# Enconder_Part1.net
KiCad netlist of a schematic drawn in Altium Designer
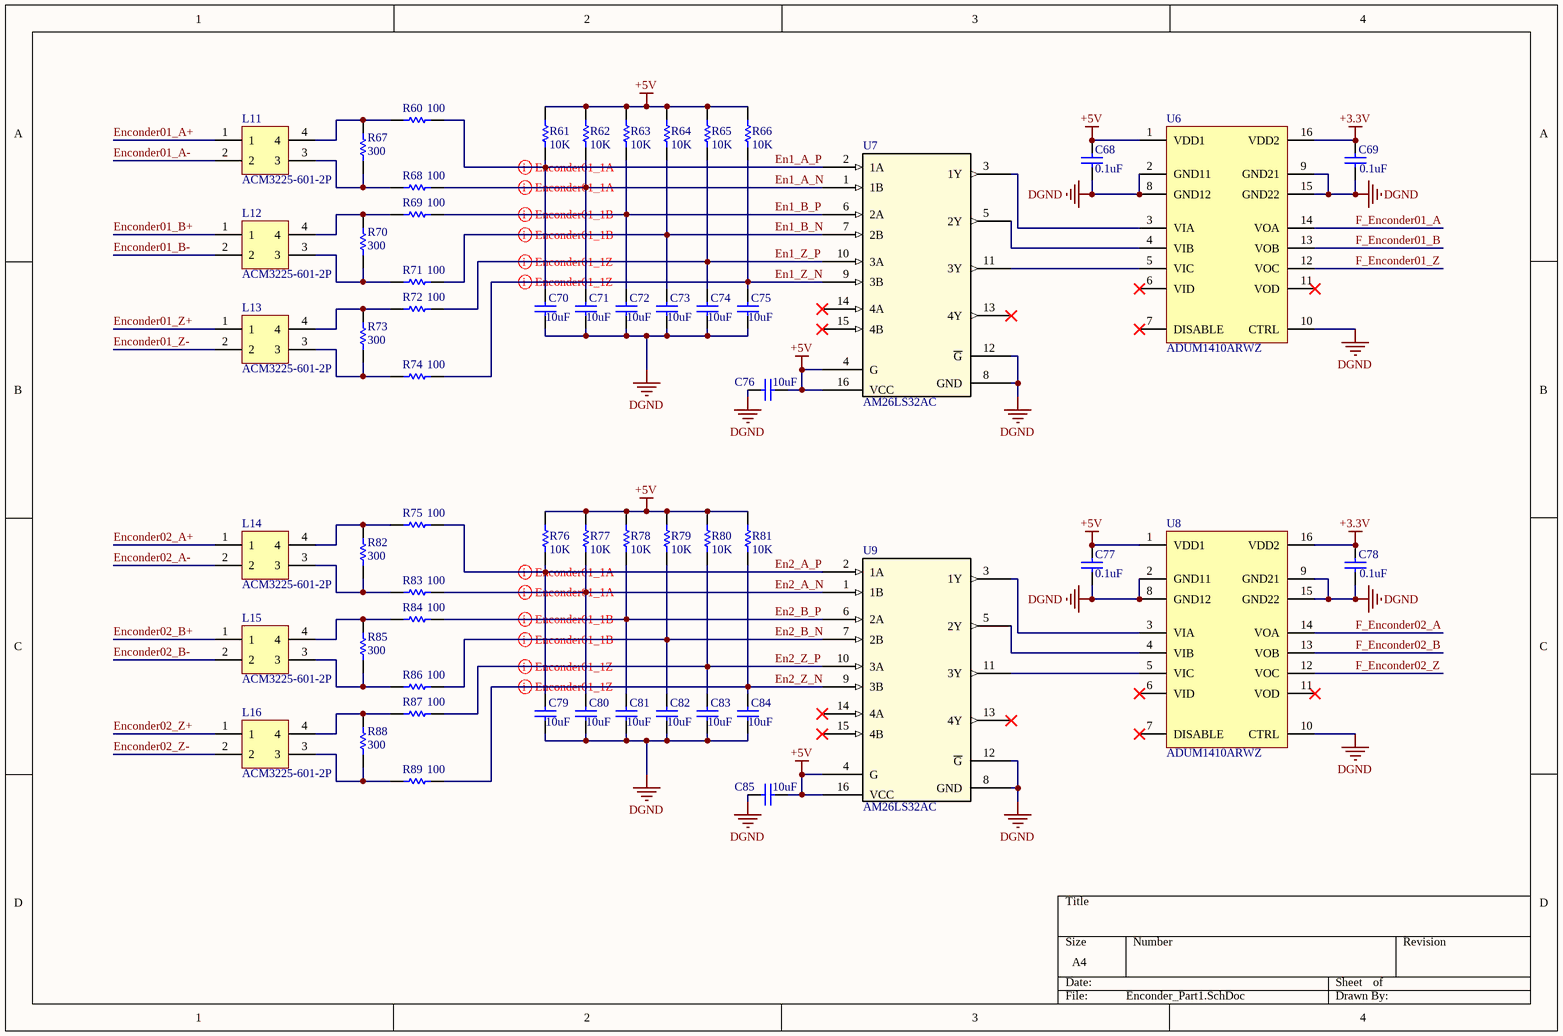
[diagram p0: Enconder_Part1.SchDoc]

(export (version "E")
  (design (tool "Eeschema 10.0.6"))
  (components
    (comp (ref "C68")
      (value "0.1uF")
      (footprint "1608[0603]")
      (description "Capacitor")
      (fields (field (name "Comment") "Cap") (field (name "PUBLISHER") "Altium Limited"))
      (libsource (lib "Miscellaneous Devices") (part "Cap"))
    )
    (comp (ref "C69")
      (value "0.1uF")
      (footprint "1608[0603]")
      (description "Capacitor")
      (fields (field (name "Comment") "Cap") (field (name "PUBLISHER") "Altium Limited"))
      (libsource (lib "Miscellaneous Devices") (part "Cap"))
    )
    (comp (ref "C70")
      (value "10uF")
      (footprint "1608[0603]")
      (description "Capacitor")
      (fields (field (name "Comment") "Cap") (field (name "PUBLISHER") "Altium Limited"))
      (libsource (lib "Miscellaneous Devices") (part "Cap"))
    )
    (comp (ref "C71")
      (value "10uF")
      (footprint "1608[0603]")
      (description "Capacitor")
      (fields (field (name "Comment") "Cap") (field (name "PUBLISHER") "Altium Limited"))
      (libsource (lib "Miscellaneous Devices") (part "Cap"))
    )
    (comp (ref "C72")
      (value "10uF")
      (footprint "1608[0603]")
      (description "Capacitor")
      (fields (field (name "Comment") "Cap") (field (name "PUBLISHER") "Altium Limited"))
      (libsource (lib "Miscellaneous Devices") (part "Cap"))
    )
    (comp (ref "C73")
      (value "10uF")
      (footprint "1608[0603]")
      (description "Capacitor")
      (fields (field (name "Comment") "Cap") (field (name "PUBLISHER") "Altium Limited"))
      (libsource (lib "Miscellaneous Devices") (part "Cap"))
    )
    (comp (ref "C74")
      (value "10uF")
      (footprint "1608[0603]")
      (description "Capacitor")
      (fields (field (name "Comment") "Cap") (field (name "PUBLISHER") "Altium Limited"))
      (libsource (lib "Miscellaneous Devices") (part "Cap"))
    )
    (comp (ref "C75")
      (value "10uF")
      (footprint "1608[0603]")
      (description "Capacitor")
      (fields (field (name "Comment") "Cap") (field (name "PUBLISHER") "Altium Limited"))
      (libsource (lib "Miscellaneous Devices") (part "Cap"))
    )
    (comp (ref "C76")
      (value "10uF")
      (footprint "1608[0603]")
      (description "Capacitor")
      (fields (field (name "Comment") "Cap") (field (name "PUBLISHER") "Altium Limited"))
      (libsource (lib "Miscellaneous Devices") (part "Cap"))
    )
    (comp (ref "C77")
      (value "0.1uF")
      (footprint "1608[0603]")
      (description "Capacitor")
      (fields (field (name "Comment") "Cap") (field (name "PUBLISHER") "Altium Limited"))
      (libsource (lib "Miscellaneous Devices") (part "Cap"))
    )
    (comp (ref "C78")
      (value "0.1uF")
      (footprint "1608[0603]")
      (description "Capacitor")
      (fields (field (name "Comment") "Cap") (field (name "PUBLISHER") "Altium Limited"))
      (libsource (lib "Miscellaneous Devices") (part "Cap"))
    )
    (comp (ref "C79")
      (value "10uF")
      (footprint "1608[0603]")
      (description "Capacitor")
      (fields (field (name "Comment") "Cap") (field (name "PUBLISHER") "Altium Limited"))
      (libsource (lib "Miscellaneous Devices") (part "Cap"))
    )
    (comp (ref "C80")
      (value "10uF")
      (footprint "1608[0603]")
      (description "Capacitor")
      (fields (field (name "Comment") "Cap") (field (name "PUBLISHER") "Altium Limited"))
      (libsource (lib "Miscellaneous Devices") (part "Cap"))
    )
    (comp (ref "C81")
      (value "10uF")
      (footprint "1608[0603]")
      (description "Capacitor")
      (fields (field (name "Comment") "Cap") (field (name "PUBLISHER") "Altium Limited"))
      (libsource (lib "Miscellaneous Devices") (part "Cap"))
    )
    (comp (ref "C82")
      (value "10uF")
      (footprint "1608[0603]")
      (description "Capacitor")
      (fields (field (name "Comment") "Cap") (field (name "PUBLISHER") "Altium Limited"))
      (libsource (lib "Miscellaneous Devices") (part "Cap"))
    )
    (comp (ref "C83")
      (value "10uF")
      (footprint "1608[0603]")
      (description "Capacitor")
      (fields (field (name "Comment") "Cap") (field (name "PUBLISHER") "Altium Limited"))
      (libsource (lib "Miscellaneous Devices") (part "Cap"))
    )
    (comp (ref "C84")
      (value "10uF")
      (footprint "1608[0603]")
      (description "Capacitor")
      (fields (field (name "Comment") "Cap") (field (name "PUBLISHER") "Altium Limited"))
      (libsource (lib "Miscellaneous Devices") (part "Cap"))
    )
    (comp (ref "C85")
      (value "10uF")
      (footprint "1608[0603]")
      (description "Capacitor")
      (fields (field (name "Comment") "Cap") (field (name "PUBLISHER") "Altium Limited"))
      (libsource (lib "Miscellaneous Devices") (part "Cap"))
    )
    (comp (ref "L11")
      (value "ACM3225-601-2P")
      (footprint "ACM3225-601-2P")
      (libsource (lib "DSP_FPGA_Lib") (part "ACM3225-601-2P"))
    )
    (comp (ref "L12")
      (value "ACM3225-601-2P")
      (footprint "ACM3225-601-2P")
      (libsource (lib "DSP_FPGA_Lib") (part "ACM3225-601-2P"))
    )
    (comp (ref "L13")
      (value "ACM3225-601-2P")
      (footprint "ACM3225-601-2P")
      (libsource (lib "DSP_FPGA_Lib") (part "ACM3225-601-2P"))
    )
    (comp (ref "L14")
      (value "ACM3225-601-2P")
      (footprint "ACM3225-601-2P")
      (libsource (lib "DSP_FPGA_Lib") (part "ACM3225-601-2P"))
    )
    (comp (ref "L15")
      (value "ACM3225-601-2P")
      (footprint "ACM3225-601-2P")
      (libsource (lib "DSP_FPGA_Lib") (part "ACM3225-601-2P"))
    )
    (comp (ref "L16")
      (value "ACM3225-601-2P")
      (footprint "ACM3225-601-2P")
      (libsource (lib "DSP_FPGA_Lib") (part "ACM3225-601-2P"))
    )
    (comp (ref "R60")
      (value "100")
      (footprint "1608[0603]")
      (description "Resistor")
      (fields (field (name "Comment") "Res1") (field (name "PUBLISHER") "Altium Limited"))
      (libsource (lib "Miscellaneous Devices") (part "Res1"))
    )
    (comp (ref "R61")
      (value "10K")
      (footprint "1608[0603]")
      (description "Resistor")
      (fields (field (name "Comment") "Res1") (field (name "PUBLISHER") "Altium Limited"))
      (libsource (lib "Miscellaneous Devices") (part "Res1"))
    )
    (comp (ref "R62")
      (value "10K")
      (footprint "1608[0603]")
      (description "Resistor")
      (fields (field (name "Comment") "Res1") (field (name "PUBLISHER") "Altium Limited"))
      (libsource (lib "Miscellaneous Devices") (part "Res1"))
    )
    (comp (ref "R63")
      (value "10K")
      (footprint "1608[0603]")
      (description "Resistor")
      (fields (field (name "Comment") "Res1") (field (name "PUBLISHER") "Altium Limited"))
      (libsource (lib "Miscellaneous Devices") (part "Res1"))
    )
    (comp (ref "R64")
      (value "10K")
      (footprint "1608[0603]")
      (description "Resistor")
      (fields (field (name "Comment") "Res1") (field (name "PUBLISHER") "Altium Limited"))
      (libsource (lib "Miscellaneous Devices") (part "Res1"))
    )
    (comp (ref "R65")
      (value "10K")
      (footprint "1608[0603]")
      (description "Resistor")
      (fields (field (name "Comment") "Res1") (field (name "PUBLISHER") "Altium Limited"))
      (libsource (lib "Miscellaneous Devices") (part "Res1"))
    )
    (comp (ref "R66")
      (value "10K")
      (footprint "1608[0603]")
      (description "Resistor")
      (fields (field (name "Comment") "Res1") (field (name "PUBLISHER") "Altium Limited"))
      (libsource (lib "Miscellaneous Devices") (part "Res1"))
    )
    (comp (ref "R67")
      (value "300")
      (footprint "1608[0603]")
      (description "Resistor")
      (fields (field (name "Comment") "Res1") (field (name "PUBLISHER") "Altium Limited"))
      (libsource (lib "Miscellaneous Devices") (part "Res1"))
    )
    (comp (ref "R68")
      (value "100")
      (footprint "1608[0603]")
      (description "Resistor")
      (fields (field (name "Comment") "Res1") (field (name "PUBLISHER") "Altium Limited"))
      (libsource (lib "Miscellaneous Devices") (part "Res1"))
    )
    (comp (ref "R69")
      (value "100")
      (footprint "1608[0603]")
      (description "Resistor")
      (fields (field (name "Comment") "Res1") (field (name "PUBLISHER") "Altium Limited"))
      (libsource (lib "Miscellaneous Devices") (part "Res1"))
    )
    (comp (ref "R70")
      (value "300")
      (footprint "1608[0603]")
      (description "Resistor")
      (fields (field (name "Comment") "Res1") (field (name "PUBLISHER") "Altium Limited"))
      (libsource (lib "Miscellaneous Devices") (part "Res1"))
    )
    (comp (ref "R71")
      (value "100")
      (footprint "1608[0603]")
      (description "Resistor")
      (fields (field (name "Comment") "Res1") (field (name "PUBLISHER") "Altium Limited"))
      (libsource (lib "Miscellaneous Devices") (part "Res1"))
    )
    (comp (ref "R72")
      (value "100")
      (footprint "1608[0603]")
      (description "Resistor")
      (fields (field (name "Comment") "Res1") (field (name "PUBLISHER") "Altium Limited"))
      (libsource (lib "Miscellaneous Devices") (part "Res1"))
    )
    (comp (ref "R73")
      (value "300")
      (footprint "1608[0603]")
      (description "Resistor")
      (fields (field (name "Comment") "Res1") (field (name "PUBLISHER") "Altium Limited"))
      (libsource (lib "Miscellaneous Devices") (part "Res1"))
    )
    (comp (ref "R74")
      (value "100")
      (footprint "1608[0603]")
      (description "Resistor")
      (fields (field (name "Comment") "Res1") (field (name "PUBLISHER") "Altium Limited"))
      (libsource (lib "Miscellaneous Devices") (part "Res1"))
    )
    (comp (ref "R75")
      (value "100")
      (footprint "1608[0603]")
      (description "Resistor")
      (fields (field (name "Comment") "Res1") (field (name "PUBLISHER") "Altium Limited"))
      (libsource (lib "Miscellaneous Devices") (part "Res1"))
    )
    (comp (ref "R76")
      (value "10K")
      (footprint "1608[0603]")
      (description "Resistor")
      (fields (field (name "Comment") "Res1") (field (name "PUBLISHER") "Altium Limited"))
      (libsource (lib "Miscellaneous Devices") (part "Res1"))
    )
    (comp (ref "R77")
      (value "10K")
      (footprint "1608[0603]")
      (description "Resistor")
      (fields (field (name "Comment") "Res1") (field (name "PUBLISHER") "Altium Limited"))
      (libsource (lib "Miscellaneous Devices") (part "Res1"))
    )
    (comp (ref "R78")
      (value "10K")
      (footprint "1608[0603]")
      (description "Resistor")
      (fields (field (name "Comment") "Res1") (field (name "PUBLISHER") "Altium Limited"))
      (libsource (lib "Miscellaneous Devices") (part "Res1"))
    )
    (comp (ref "R79")
      (value "10K")
      (footprint "1608[0603]")
      (description "Resistor")
      (fields (field (name "Comment") "Res1") (field (name "PUBLISHER") "Altium Limited"))
      (libsource (lib "Miscellaneous Devices") (part "Res1"))
    )
    (comp (ref "R80")
      (value "10K")
      (footprint "1608[0603]")
      (description "Resistor")
      (fields (field (name "Comment") "Res1") (field (name "PUBLISHER") "Altium Limited"))
      (libsource (lib "Miscellaneous Devices") (part "Res1"))
    )
    (comp (ref "R81")
      (value "10K")
      (footprint "1608[0603]")
      (description "Resistor")
      (fields (field (name "Comment") "Res1") (field (name "PUBLISHER") "Altium Limited"))
      (libsource (lib "Miscellaneous Devices") (part "Res1"))
    )
    (comp (ref "R82")
      (value "300")
      (footprint "1608[0603]")
      (description "Resistor")
      (fields (field (name "Comment") "Res1") (field (name "PUBLISHER") "Altium Limited"))
      (libsource (lib "Miscellaneous Devices") (part "Res1"))
    )
    (comp (ref "R83")
      (value "100")
      (footprint "1608[0603]")
      (description "Resistor")
      (fields (field (name "Comment") "Res1") (field (name "PUBLISHER") "Altium Limited"))
      (libsource (lib "Miscellaneous Devices") (part "Res1"))
    )
    (comp (ref "R84")
      (value "100")
      (footprint "1608[0603]")
      (description "Resistor")
      (fields (field (name "Comment") "Res1") (field (name "PUBLISHER") "Altium Limited"))
      (libsource (lib "Miscellaneous Devices") (part "Res1"))
    )
    (comp (ref "R85")
      (value "300")
      (footprint "1608[0603]")
      (description "Resistor")
      (fields (field (name "Comment") "Res1") (field (name "PUBLISHER") "Altium Limited"))
      (libsource (lib "Miscellaneous Devices") (part "Res1"))
    )
    (comp (ref "R86")
      (value "100")
      (footprint "1608[0603]")
      (description "Resistor")
      (fields (field (name "Comment") "Res1") (field (name "PUBLISHER") "Altium Limited"))
      (libsource (lib "Miscellaneous Devices") (part "Res1"))
    )
    (comp (ref "R87")
      (value "100")
      (footprint "1608[0603]")
      (description "Resistor")
      (fields (field (name "Comment") "Res1") (field (name "PUBLISHER") "Altium Limited"))
      (libsource (lib "Miscellaneous Devices") (part "Res1"))
    )
    (comp (ref "R88")
      (value "300")
      (footprint "1608[0603]")
      (description "Resistor")
      (fields (field (name "Comment") "Res1") (field (name "PUBLISHER") "Altium Limited"))
      (libsource (lib "Miscellaneous Devices") (part "Res1"))
    )
    (comp (ref "R89")
      (value "100")
      (footprint "1608[0603]")
      (description "Resistor")
      (fields (field (name "Comment") "Res1") (field (name "PUBLISHER") "Altium Limited"))
      (libsource (lib "Miscellaneous Devices") (part "Res1"))
    )
    (comp (ref "U6")
      (value "ADUM1410ARWZ")
      (footprint "ADUM1410ARWZ_SOIC")
      (libsource (lib "DSP_FPGA_Lib") (part "ADUM1410ARWZ"))
    )
    (comp (ref "U7")
      (value "AM26LS32AC")
      (footprint "AM26LS32AC_SOP")
      (libsource (lib "DSP_FPGA_Lib") (part "AM26LS32AC"))
    )
    (comp (ref "U8")
      (value "ADUM1410ARWZ")
      (footprint "ADUM1410ARWZ_SOIC")
      (libsource (lib "DSP_FPGA_Lib") (part "ADUM1410ARWZ"))
    )
    (comp (ref "U9")
      (value "AM26LS32AC")
      (footprint "AM26LS32AC_SOP")
      (libsource (lib "DSP_FPGA_Lib") (part "AM26LS32AC"))
    )
  )
  (nets
    (net (code "1") (name "+3.3V") (class "Default")
      (node (ref "C69") (pin "2") (pinfunction "2_2") (pintype "passive"))
      (node (ref "C78") (pin "2") (pinfunction "2_2") (pintype "passive"))
      (node (ref "U6") (pin "16") (pinfunction "VDD2_16") (pintype "passive"))
      (node (ref "U8") (pin "16") (pinfunction "VDD2_16") (pintype "passive"))
    )
    (net (code "2") (name "+5V") (class "Default")
      (node (ref "C68") (pin "2") (pinfunction "2_2") (pintype "passive"))
      (node (ref "C76") (pin "1") (pinfunction "1_1") (pintype "passive"))
      (node (ref "C77") (pin "2") (pinfunction "2_2") (pintype "passive"))
      (node (ref "C85") (pin "1") (pinfunction "1_1") (pintype "passive"))
      (node (ref "R61") (pin "2") (pinfunction "2_2") (pintype "passive"))
      (node (ref "R62") (pin "2") (pinfunction "2_2") (pintype "passive"))
      (node (ref "R63") (pin "2") (pinfunction "2_2") (pintype "passive"))
      (node (ref "R64") (pin "2") (pinfunction "2_2") (pintype "passive"))
      (node (ref "R65") (pin "2") (pinfunction "2_2") (pintype "passive"))
      (node (ref "R66") (pin "2") (pinfunction "2_2") (pintype "passive"))
      (node (ref "R76") (pin "2") (pinfunction "2_2") (pintype "passive"))
      (node (ref "R77") (pin "2") (pinfunction "2_2") (pintype "passive"))
      (node (ref "R78") (pin "2") (pinfunction "2_2") (pintype "passive"))
      (node (ref "R79") (pin "2") (pinfunction "2_2") (pintype "passive"))
      (node (ref "R80") (pin "2") (pinfunction "2_2") (pintype "passive"))
      (node (ref "R81") (pin "2") (pinfunction "2_2") (pintype "passive"))
      (node (ref "U6") (pin "1") (pinfunction "VDD1_1") (pintype "passive"))
      (node (ref "U7") (pin "16") (pinfunction "VCC_16") (pintype "power_in"))
      (node (ref "U7") (pin "4") (pinfunction "G_4") (pintype "passive"))
      (node (ref "U8") (pin "1") (pinfunction "VDD1_1") (pintype "passive"))
      (node (ref "U9") (pin "16") (pinfunction "VCC_16") (pintype "power_in"))
      (node (ref "U9") (pin "4") (pinfunction "G_4") (pintype "passive"))
    )
    (net (code "3") (name "/En1_A_N") (class "Default")
      (node (ref "C71") (pin "2") (pinfunction "2_2") (pintype "passive"))
      (node (ref "R62") (pin "1") (pinfunction "1_1") (pintype "passive"))
      (node (ref "R68") (pin "2") (pinfunction "2_2") (pintype "passive"))
      (node (ref "U7") (pin "1") (pinfunction "1B_1") (pintype "input"))
    )
    (net (code "4") (name "/En1_A_P") (class "Default")
      (node (ref "C70") (pin "2") (pinfunction "2_2") (pintype "passive"))
      (node (ref "R60") (pin "2") (pinfunction "2_2") (pintype "passive"))
      (node (ref "R61") (pin "1") (pinfunction "1_1") (pintype "passive"))
      (node (ref "U7") (pin "2") (pinfunction "1A_2") (pintype "input"))
    )
    (net (code "5") (name "/En1_B_N") (class "Default")
      (node (ref "C73") (pin "2") (pinfunction "2_2") (pintype "passive"))
      (node (ref "R64") (pin "1") (pinfunction "1_1") (pintype "passive"))
      (node (ref "R71") (pin "2") (pinfunction "2_2") (pintype "passive"))
      (node (ref "U7") (pin "7") (pinfunction "2B_7") (pintype "input"))
    )
    (net (code "6") (name "/En1_B_P") (class "Default")
      (node (ref "C72") (pin "2") (pinfunction "2_2") (pintype "passive"))
      (node (ref "R63") (pin "1") (pinfunction "1_1") (pintype "passive"))
      (node (ref "R69") (pin "2") (pinfunction "2_2") (pintype "passive"))
      (node (ref "U7") (pin "6") (pinfunction "2A_6") (pintype "input"))
    )
    (net (code "7") (name "/En1_Z_N") (class "Default")
      (node (ref "C75") (pin "2") (pinfunction "2_2") (pintype "passive"))
      (node (ref "R66") (pin "1") (pinfunction "1_1") (pintype "passive"))
      (node (ref "R74") (pin "2") (pinfunction "2_2") (pintype "passive"))
      (node (ref "U7") (pin "9") (pinfunction "3B_9") (pintype "input"))
    )
    (net (code "8") (name "/En1_Z_P") (class "Default")
      (node (ref "C74") (pin "2") (pinfunction "2_2") (pintype "passive"))
      (node (ref "R65") (pin "1") (pinfunction "1_1") (pintype "passive"))
      (node (ref "R72") (pin "2") (pinfunction "2_2") (pintype "passive"))
      (node (ref "U7") (pin "10") (pinfunction "3A_10") (pintype "input"))
    )
    (net (code "9") (name "/En2_A_N") (class "Default")
      (node (ref "C80") (pin "2") (pinfunction "2_2") (pintype "passive"))
      (node (ref "R77") (pin "1") (pinfunction "1_1") (pintype "passive"))
      (node (ref "R83") (pin "2") (pinfunction "2_2") (pintype "passive"))
      (node (ref "U9") (pin "1") (pinfunction "1B_1") (pintype "input"))
    )
    (net (code "10") (name "/En2_A_P") (class "Default")
      (node (ref "C79") (pin "2") (pinfunction "2_2") (pintype "passive"))
      (node (ref "R75") (pin "2") (pinfunction "2_2") (pintype "passive"))
      (node (ref "R76") (pin "1") (pinfunction "1_1") (pintype "passive"))
      (node (ref "U9") (pin "2") (pinfunction "1A_2") (pintype "input"))
    )
    (net (code "11") (name "/En2_B_N") (class "Default")
      (node (ref "C82") (pin "2") (pinfunction "2_2") (pintype "passive"))
      (node (ref "R79") (pin "1") (pinfunction "1_1") (pintype "passive"))
      (node (ref "R86") (pin "2") (pinfunction "2_2") (pintype "passive"))
      (node (ref "U9") (pin "7") (pinfunction "2B_7") (pintype "input"))
    )
    (net (code "12") (name "/En2_B_P") (class "Default")
      (node (ref "C81") (pin "2") (pinfunction "2_2") (pintype "passive"))
      (node (ref "R78") (pin "1") (pinfunction "1_1") (pintype "passive"))
      (node (ref "R84") (pin "2") (pinfunction "2_2") (pintype "passive"))
      (node (ref "U9") (pin "6") (pinfunction "2A_6") (pintype "input"))
    )
    (net (code "13") (name "/En2_Z_N") (class "Default")
      (node (ref "C84") (pin "2") (pinfunction "2_2") (pintype "passive"))
      (node (ref "R81") (pin "1") (pinfunction "1_1") (pintype "passive"))
      (node (ref "R89") (pin "2") (pinfunction "2_2") (pintype "passive"))
      (node (ref "U9") (pin "9") (pinfunction "3B_9") (pintype "input"))
    )
    (net (code "14") (name "/En2_Z_P") (class "Default")
      (node (ref "C83") (pin "2") (pinfunction "2_2") (pintype "passive"))
      (node (ref "R80") (pin "1") (pinfunction "1_1") (pintype "passive"))
      (node (ref "R87") (pin "2") (pinfunction "2_2") (pintype "passive"))
      (node (ref "U9") (pin "10") (pinfunction "3A_10") (pintype "input"))
    )
    (net (code "15") (name "/Enconder01_A+") (class "Default")
      (node (ref "L11") (pin "1") (pinfunction "1_1") (pintype "passive"))
    )
    (net (code "16") (name "/Enconder01_A-") (class "Default")
      (node (ref "L11") (pin "2") (pinfunction "2_2") (pintype "passive"))
    )
    (net (code "17") (name "/Enconder01_B+") (class "Default")
      (node (ref "L12") (pin "1") (pinfunction "1_1") (pintype "passive"))
    )
    (net (code "18") (name "/Enconder01_B-") (class "Default")
      (node (ref "L12") (pin "2") (pinfunction "2_2") (pintype "passive"))
    )
    (net (code "19") (name "/Enconder01_Z+") (class "Default")
      (node (ref "L13") (pin "1") (pinfunction "1_1") (pintype "passive"))
    )
    (net (code "20") (name "/Enconder01_Z-") (class "Default")
      (node (ref "L13") (pin "2") (pinfunction "2_2") (pintype "passive"))
    )
    (net (code "21") (name "/Enconder02_A+") (class "Default")
      (node (ref "L14") (pin "1") (pinfunction "1_1") (pintype "passive"))
    )
    (net (code "22") (name "/Enconder02_A-") (class "Default")
      (node (ref "L14") (pin "2") (pinfunction "2_2") (pintype "passive"))
    )
    (net (code "23") (name "/Enconder02_B+") (class "Default")
      (node (ref "L15") (pin "1") (pinfunction "1_1") (pintype "passive"))
    )
    (net (code "24") (name "/Enconder02_B-") (class "Default")
      (node (ref "L15") (pin "2") (pinfunction "2_2") (pintype "passive"))
    )
    (net (code "25") (name "/Enconder02_Z+") (class "Default")
      (node (ref "L16") (pin "1") (pinfunction "1_1") (pintype "passive"))
    )
    (net (code "26") (name "/Enconder02_Z-") (class "Default")
      (node (ref "L16") (pin "2") (pinfunction "2_2") (pintype "passive"))
    )
    (net (code "27") (name "/F_Enconder01_A") (class "Default")
      (node (ref "U6") (pin "14") (pinfunction "VOA_14") (pintype "passive"))
    )
    (net (code "28") (name "/F_Enconder01_B") (class "Default")
      (node (ref "U6") (pin "13") (pinfunction "VOB_13") (pintype "passive"))
    )
    (net (code "29") (name "/F_Enconder01_Z") (class "Default")
      (node (ref "U6") (pin "12") (pinfunction "VOC_12") (pintype "passive"))
    )
    (net (code "30") (name "/F_Enconder02_A") (class "Default")
      (node (ref "U8") (pin "14") (pinfunction "VOA_14") (pintype "passive"))
    )
    (net (code "31") (name "/F_Enconder02_B") (class "Default")
      (node (ref "U8") (pin "13") (pinfunction "VOB_13") (pintype "passive"))
    )
    (net (code "32") (name "/F_Enconder02_Z") (class "Default")
      (node (ref "U8") (pin "12") (pinfunction "VOC_12") (pintype "passive"))
    )
    (net (code "33") (name "DGND") (class "Default")
      (node (ref "C68") (pin "1") (pinfunction "1_1") (pintype "passive"))
      (node (ref "C69") (pin "1") (pinfunction "1_1") (pintype "passive"))
      (node (ref "C70") (pin "1") (pinfunction "1_1") (pintype "passive"))
      (node (ref "C71") (pin "1") (pinfunction "1_1") (pintype "passive"))
      (node (ref "C72") (pin "1") (pinfunction "1_1") (pintype "passive"))
      (node (ref "C73") (pin "1") (pinfunction "1_1") (pintype "passive"))
      (node (ref "C74") (pin "1") (pinfunction "1_1") (pintype "passive"))
      (node (ref "C75") (pin "1") (pinfunction "1_1") (pintype "passive"))
      (node (ref "C76") (pin "2") (pinfunction "2_2") (pintype "passive"))
      (node (ref "C77") (pin "1") (pinfunction "1_1") (pintype "passive"))
      (node (ref "C78") (pin "1") (pinfunction "1_1") (pintype "passive"))
      (node (ref "C79") (pin "1") (pinfunction "1_1") (pintype "passive"))
      (node (ref "C80") (pin "1") (pinfunction "1_1") (pintype "passive"))
      (node (ref "C81") (pin "1") (pinfunction "1_1") (pintype "passive"))
      (node (ref "C82") (pin "1") (pinfunction "1_1") (pintype "passive"))
      (node (ref "C83") (pin "1") (pinfunction "1_1") (pintype "passive"))
      (node (ref "C84") (pin "1") (pinfunction "1_1") (pintype "passive"))
      (node (ref "C85") (pin "2") (pinfunction "2_2") (pintype "passive"))
      (node (ref "U6") (pin "10") (pinfunction "CTRL_10") (pintype "passive"))
      (node (ref "U6") (pin "15") (pinfunction "GND22_15") (pintype "passive"))
      (node (ref "U6") (pin "2") (pinfunction "GND11_2") (pintype "passive"))
      (node (ref "U6") (pin "8") (pinfunction "GND12_8") (pintype "passive"))
      (node (ref "U6") (pin "9") (pinfunction "GND21_9") (pintype "passive"))
      (node (ref "U7") (pin "12") (pinfunction "~{G}_12") (pintype "passive"))
      (node (ref "U7") (pin "8") (pinfunction "GND_8") (pintype "power_in"))
      (node (ref "U8") (pin "10") (pinfunction "CTRL_10") (pintype "passive"))
      (node (ref "U8") (pin "15") (pinfunction "GND22_15") (pintype "passive"))
      (node (ref "U8") (pin "2") (pinfunction "GND11_2") (pintype "passive"))
      (node (ref "U8") (pin "8") (pinfunction "GND12_8") (pintype "passive"))
      (node (ref "U8") (pin "9") (pinfunction "GND21_9") (pintype "passive"))
      (node (ref "U9") (pin "12") (pinfunction "~{G}_12") (pintype "passive"))
      (node (ref "U9") (pin "8") (pinfunction "GND_8") (pintype "power_in"))
    )
    (net (code "34") (name "Net-(L11-Pad3)") (class "Default")
      (node (ref "L11") (pin "3") (pinfunction "3_3") (pintype "passive"))
      (node (ref "R67") (pin "1") (pinfunction "1_1") (pintype "passive"))
      (node (ref "R68") (pin "1") (pinfunction "1_1") (pintype "passive"))
    )
    (net (code "35") (name "Net-(L11-Pad4)") (class "Default")
      (node (ref "L11") (pin "4") (pinfunction "4_4") (pintype "passive"))
      (node (ref "R60") (pin "1") (pinfunction "1_1") (pintype "passive"))
      (node (ref "R67") (pin "2") (pinfunction "2_2") (pintype "passive"))
    )
    (net (code "36") (name "Net-(L12-Pad3)") (class "Default")
      (node (ref "L12") (pin "3") (pinfunction "3_3") (pintype "passive"))
      (node (ref "R70") (pin "1") (pinfunction "1_1") (pintype "passive"))
      (node (ref "R71") (pin "1") (pinfunction "1_1") (pintype "passive"))
    )
    (net (code "37") (name "Net-(L12-Pad4)") (class "Default")
      (node (ref "L12") (pin "4") (pinfunction "4_4") (pintype "passive"))
      (node (ref "R69") (pin "1") (pinfunction "1_1") (pintype "passive"))
      (node (ref "R70") (pin "2") (pinfunction "2_2") (pintype "passive"))
    )
    (net (code "38") (name "Net-(L13-Pad3)") (class "Default")
      (node (ref "L13") (pin "3") (pinfunction "3_3") (pintype "passive"))
      (node (ref "R73") (pin "1") (pinfunction "1_1") (pintype "passive"))
      (node (ref "R74") (pin "1") (pinfunction "1_1") (pintype "passive"))
    )
    (net (code "39") (name "Net-(L13-Pad4)") (class "Default")
      (node (ref "L13") (pin "4") (pinfunction "4_4") (pintype "passive"))
      (node (ref "R72") (pin "1") (pinfunction "1_1") (pintype "passive"))
      (node (ref "R73") (pin "2") (pinfunction "2_2") (pintype "passive"))
    )
    (net (code "40") (name "Net-(L14-Pad3)") (class "Default")
      (node (ref "L14") (pin "3") (pinfunction "3_3") (pintype "passive"))
      (node (ref "R82") (pin "1") (pinfunction "1_1") (pintype "passive"))
      (node (ref "R83") (pin "1") (pinfunction "1_1") (pintype "passive"))
    )
    (net (code "41") (name "Net-(L14-Pad4)") (class "Default")
      (node (ref "L14") (pin "4") (pinfunction "4_4") (pintype "passive"))
      (node (ref "R75") (pin "1") (pinfunction "1_1") (pintype "passive"))
      (node (ref "R82") (pin "2") (pinfunction "2_2") (pintype "passive"))
    )
    (net (code "42") (name "Net-(L15-Pad3)") (class "Default")
      (node (ref "L15") (pin "3") (pinfunction "3_3") (pintype "passive"))
      (node (ref "R85") (pin "1") (pinfunction "1_1") (pintype "passive"))
      (node (ref "R86") (pin "1") (pinfunction "1_1") (pintype "passive"))
    )
    (net (code "43") (name "Net-(L15-Pad4)") (class "Default")
      (node (ref "L15") (pin "4") (pinfunction "4_4") (pintype "passive"))
      (node (ref "R84") (pin "1") (pinfunction "1_1") (pintype "passive"))
      (node (ref "R85") (pin "2") (pinfunction "2_2") (pintype "passive"))
    )
    (net (code "44") (name "Net-(L16-Pad3)") (class "Default")
      (node (ref "L16") (pin "3") (pinfunction "3_3") (pintype "passive"))
      (node (ref "R88") (pin "1") (pinfunction "1_1") (pintype "passive"))
      (node (ref "R89") (pin "1") (pinfunction "1_1") (pintype "passive"))
    )
    (net (code "45") (name "Net-(L16-Pad4)") (class "Default")
      (node (ref "L16") (pin "4") (pinfunction "4_4") (pintype "passive"))
      (node (ref "R87") (pin "1") (pinfunction "1_1") (pintype "passive"))
      (node (ref "R88") (pin "2") (pinfunction "2_2") (pintype "passive"))
    )
    (net (code "46") (name "Net-(U6-VIA)") (class "Default")
      (node (ref "U6") (pin "3") (pinfunction "VIA_3") (pintype "passive"))
      (node (ref "U7") (pin "3") (pinfunction "1Y_3") (pintype "output"))
    )
    (net (code "47") (name "Net-(U6-VIB)") (class "Default")
      (node (ref "U6") (pin "4") (pinfunction "VIB_4") (pintype "passive"))
      (node (ref "U7") (pin "5") (pinfunction "2Y_5") (pintype "output"))
    )
    (net (code "48") (name "Net-(U6-VIC)") (class "Default")
      (node (ref "U6") (pin "5") (pinfunction "VIC_5") (pintype "passive"))
      (node (ref "U7") (pin "11") (pinfunction "3Y_11") (pintype "output"))
    )
    (net (code "49") (name "Net-(U8-VIA)") (class "Default")
      (node (ref "U8") (pin "3") (pinfunction "VIA_3") (pintype "passive"))
      (node (ref "U9") (pin "3") (pinfunction "1Y_3") (pintype "output"))
    )
    (net (code "50") (name "Net-(U8-VIB)") (class "Default")
      (node (ref "U8") (pin "4") (pinfunction "VIB_4") (pintype "passive"))
      (node (ref "U9") (pin "5") (pinfunction "2Y_5") (pintype "output"))
    )
    (net (code "51") (name "Net-(U8-VIC)") (class "Default")
      (node (ref "U8") (pin "5") (pinfunction "VIC_5") (pintype "passive"))
      (node (ref "U9") (pin "11") (pinfunction "3Y_11") (pintype "output"))
    )
    (net (code "52") (name "unconnected-(U6-DISABLE-Pad7)") (class "Default")
      (node (ref "U6") (pin "7") (pinfunction "DISABLE_7") (pintype "passive+no_connect"))
    )
    (net (code "53") (name "unconnected-(U6-VID-Pad6)") (class "Default")
      (node (ref "U6") (pin "6") (pinfunction "VID_6") (pintype "passive+no_connect"))
    )
    (net (code "54") (name "unconnected-(U6-VOD-Pad11)") (class "Default")
      (node (ref "U6") (pin "11") (pinfunction "VOD_11") (pintype "passive+no_connect"))
    )
    (net (code "55") (name "unconnected-(U7-4A-Pad14)") (class "Default")
      (node (ref "U7") (pin "14") (pinfunction "4A_14") (pintype "input+no_connect"))
    )
    (net (code "56") (name "unconnected-(U7-4B-Pad15)") (class "Default")
      (node (ref "U7") (pin "15") (pinfunction "4B_15") (pintype "input+no_connect"))
    )
    (net (code "57") (name "unconnected-(U7-4Y-Pad13)") (class "Default")
      (node (ref "U7") (pin "13") (pinfunction "4Y_13") (pintype "output+no_connect"))
    )
    (net (code "58") (name "unconnected-(U8-DISABLE-Pad7)") (class "Default")
      (node (ref "U8") (pin "7") (pinfunction "DISABLE_7") (pintype "passive+no_connect"))
    )
    (net (code "59") (name "unconnected-(U8-VID-Pad6)") (class "Default")
      (node (ref "U8") (pin "6") (pinfunction "VID_6") (pintype "passive+no_connect"))
    )
    (net (code "60") (name "unconnected-(U8-VOD-Pad11)") (class "Default")
      (node (ref "U8") (pin "11") (pinfunction "VOD_11") (pintype "passive+no_connect"))
    )
    (net (code "61") (name "unconnected-(U9-4A-Pad14)") (class "Default")
      (node (ref "U9") (pin "14") (pinfunction "4A_14") (pintype "input+no_connect"))
    )
    (net (code "62") (name "unconnected-(U9-4B-Pad15)") (class "Default")
      (node (ref "U9") (pin "15") (pinfunction "4B_15") (pintype "input+no_connect"))
    )
    (net (code "63") (name "unconnected-(U9-4Y-Pad13)") (class "Default")
      (node (ref "U9") (pin "13") (pinfunction "4Y_13") (pintype "output+no_connect"))
    )
  )
)
